# SidePanel.net
KiCad netlist of a schematic drawn in Altium Designer
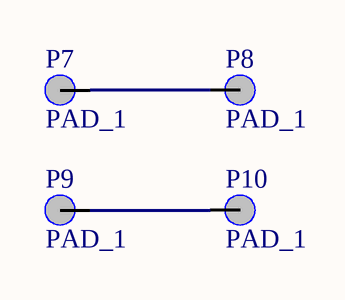
[diagram p0: SidePanel.SchDoc]

(export (version "E")
  (design (tool "Eeschema 10.0.6"))
  (components
    (comp (ref "P7")
      (value "PAD_1")
      (footprint "Pad_Pin_1")
      (description "1脚焊盘")
      (libsource (lib "Levent_lib_commons") (part "PAD_1"))
    )
    (comp (ref "P8")
      (value "PAD_1")
      (footprint "Pad_Pin_1")
      (description "1脚焊盘")
      (libsource (lib "Levent_lib_commons") (part "PAD_1"))
    )
    (comp (ref "P9")
      (value "PAD_1")
      (footprint "Pad_Pin_1")
      (description "1脚焊盘")
      (libsource (lib "Levent_lib_commons") (part "PAD_1"))
    )
    (comp (ref "P10")
      (value "PAD_1")
      (footprint "Pad_Pin_1")
      (description "1脚焊盘")
      (libsource (lib "Levent_lib_commons") (part "PAD_1"))
    )
  )
  (nets
    (net (code "1") (name "Net-(P7-Pad1)") (class "Default")
      (node (ref "P7") (pin "1") (pinfunction "1_1") (pintype "passive"))
      (node (ref "P8") (pin "1") (pinfunction "1_1") (pintype "passive"))
    )
    (net (code "2") (name "Net-(P10-Pad1)") (class "Default")
      (node (ref "P10") (pin "1") (pinfunction "1_1") (pintype "passive"))
      (node (ref "P9") (pin "1") (pinfunction "1_1") (pintype "passive"))
    )
  )
)
